# relay.net
KiCad netlist of a schematic drawn in EAGLE
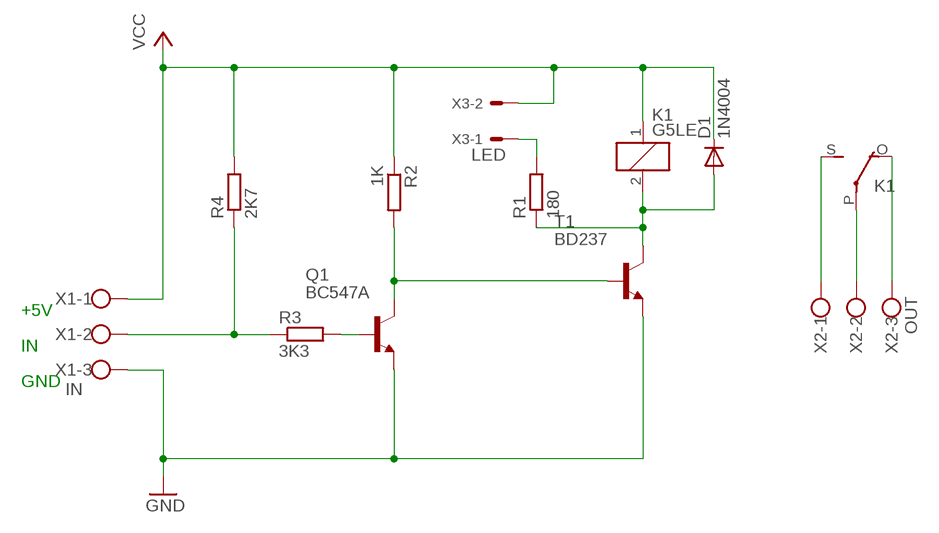
[diagram p0: schematic, sheet 1]

(export (version "E")
  (design (tool "Eeschema 10.0.6"))
  (components
    (comp (ref "D1")
      (value "1N4004")
      (footprint "eagle-import:DO41-10")
      (libsource (lib "eagle-import") (part "1N4004"))
    )
    (comp (ref "K1")
      (value "G5LE")
      (footprint "eagle-import:G5LE")
      (libsource (lib "eagle-import") (part "G5LE"))
    )
    (comp (ref "Q1")
      (value "BC547A")
      (footprint "eagle-import:TO92")
      (libsource (lib "eagle-import") (part "BC547A"))
    )
    (comp (ref "R1")
      (value "180")
      (footprint "eagle-import:0207_10")
      (libsource (lib "eagle-import") (part "R-EU_0207/10"))
    )
    (comp (ref "R2")
      (value "1K")
      (footprint "eagle-import:0207_7")
      (libsource (lib "eagle-import") (part "resistor_R-EU_0207/7"))
    )
    (comp (ref "R3")
      (value "3K3")
      (footprint "eagle-import:0207_10")
      (libsource (lib "eagle-import") (part "R-EU_0207/10"))
    )
    (comp (ref "R4")
      (value "2K7")
      (footprint "eagle-import:0207_10")
      (libsource (lib "eagle-import") (part "R-EU_0207/10"))
    )
    (comp (ref "T1")
      (value "BD237")
      (footprint "eagle-import:TO126V")
      (libsource (lib "eagle-import") (part "-NPN-TO126V"))
    )
    (comp (ref "X1")
      (value "IN")
      (footprint "eagle-import:AK550_3")
      (libsource (lib "eagle-import") (part "AK550/3"))
    )
    (comp (ref "X2")
      (value "OUT")
      (footprint "eagle-import:W237-103")
      (fields (field (name "MPN") "237-103"))
      (libsource (lib "eagle-import") (part "W237-103"))
    )
    (comp (ref "X3")
      (value "LED")
      (footprint "eagle-import:6410-02")
      (libsource (lib "eagle-import") (part "22-?-0227-2021"))
    )
  )
  (nets
    (net (code "1") (name "GND") (class "Default")
      (node (ref "Q1") (pin "1") (pinfunction "E_1") (pintype "passive"))
      (node (ref "T1") (pin "1") (pinfunction "E_1") (pintype "passive"))
      (node (ref "X1") (pin "3") (pinfunction "KL_3") (pintype "passive"))
    )
    (net (code "2") (name "Net-(Q1-B)") (class "Default")
      (node (ref "Q1") (pin "2") (pinfunction "B_2") (pintype "passive"))
      (node (ref "R3") (pin "2") (pinfunction "2_2") (pintype "passive"))
    )
    (net (code "3") (name "Net-(Q1-C)") (class "Default")
      (node (ref "Q1") (pin "3") (pinfunction "C_3") (pintype "passive"))
      (node (ref "R2") (pin "2") (pinfunction "2_2") (pintype "passive"))
      (node (ref "T1") (pin "3") (pinfunction "B_3") (pintype "passive"))
    )
    (net (code "4") (name "Net-(T1-C)") (class "Default")
      (node (ref "D1") (pin "A") (pinfunction "A_A") (pintype "passive"))
      (node (ref "K1") (pin "2") (pinfunction "2_2") (pintype "passive"))
      (node (ref "R1") (pin "1") (pinfunction "1_1") (pintype "passive"))
      (node (ref "T1") (pin "2") (pinfunction "C_2") (pintype "passive"))
    )
    (net (code "5") (name "Net-(X1B-KL)") (class "Default")
      (node (ref "R3") (pin "1") (pinfunction "1_1") (pintype "passive"))
      (node (ref "R4") (pin "1") (pinfunction "1_1") (pintype "passive"))
      (node (ref "X1") (pin "2") (pinfunction "KL_2") (pintype "passive"))
    )
    (net (code "6") (name "Net-(X2A-KL)") (class "Default")
      (node (ref "K1") (pin "S") (pinfunction "S_S") (pintype "passive"))
      (node (ref "X2") (pin "1") (pinfunction "KL_1") (pintype "passive"))
    )
    (net (code "7") (name "Net-(X2B-KL)") (class "Default")
      (node (ref "K1") (pin "P") (pinfunction "P_P") (pintype "passive"))
      (node (ref "X2") (pin "2") (pinfunction "KL_2") (pintype "passive"))
    )
    (net (code "8") (name "Net-(X2C-KL)") (class "Default")
      (node (ref "K1") (pin "O") (pinfunction "O_O") (pintype "passive"))
      (node (ref "X2") (pin "3") (pinfunction "KL_3") (pintype "passive"))
    )
    (net (code "9") (name "Net-(X3A-S)") (class "Default")
      (node (ref "R1") (pin "2") (pinfunction "2_2") (pintype "passive"))
      (node (ref "X3") (pin "1") (pinfunction "S_1") (pintype "passive"))
    )
    (net (code "10") (name "VCC") (class "Default")
      (node (ref "D1") (pin "C") (pinfunction "C_C") (pintype "passive"))
      (node (ref "K1") (pin "1") (pinfunction "1_1") (pintype "passive"))
      (node (ref "R2") (pin "1") (pinfunction "1_1") (pintype "passive"))
      (node (ref "R4") (pin "2") (pinfunction "2_2") (pintype "passive"))
      (node (ref "X1") (pin "1") (pinfunction "KL_1") (pintype "passive"))
      (node (ref "X3") (pin "2") (pinfunction "S_2") (pintype "passive"))
    )
  )
)
